# Breath.net
KiCad netlist of a schematic drawn in Altium Designer
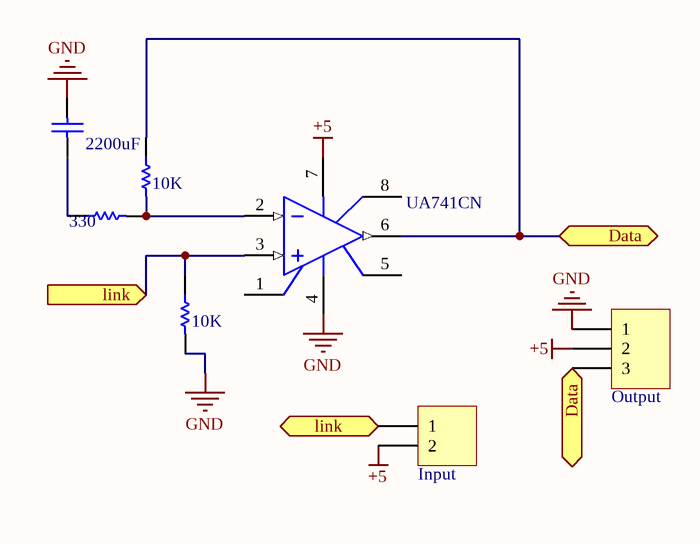
[diagram p0: Breath.SchDoc]

(export (version "E")
  (design (tool "Eeschema 10.0.6"))
  (components
    (comp (ref "10K Juga")
      (value "10K")
      (footprint "AXIAL-0.3")
      (description "Resistor")
      (fields (field (name "PUBLISHER") "Altium Limited"))
      (libsource (lib "Miscellaneous Devices") (part "Res1"))
    )
    (comp (ref "10K-2")
      (value "10K")
      (footprint "AXIAL-0.3")
      (description "Resistor")
      (fields (field (name "PUBLISHER") "Altium Limited"))
      (libsource (lib "Miscellaneous Devices") (part "Res1"))
    )
    (comp (ref "330-2")
      (value "330")
      (footprint "AXIAL-0.3")
      (description "Resistor")
      (fields (field (name "PUBLISHER") "Altium Limited"))
      (libsource (lib "Miscellaneous Devices") (part "Res1"))
    )
    (comp (ref "2200uF")
      (value "2200uF")
      (footprint "RAD-0.3")
      (description "Capacitor")
      (fields (field (name "PUBLISHER") "Altium Limited"))
      (libsource (lib "Miscellaneous Devices") (part "Cap"))
    )
    (comp (ref "o")
      (value "Output")
      (footprint "My_1X03")
      (description "Header, 3-Pin")
      (fields (field (name "PUBLISHER") "Altium Limited"))
      (libsource (lib "Mylib") (part "Header 3"))
    )
    (comp (ref "PPP")
      (value "Input")
      (footprint "HDR1X2")
      (description "Header, 2-Pin")
      (fields (field (name "PUBLISHER") "Altium Limited"))
      (libsource (lib "Mylib") (part "Header 2"))
    )
    (comp (ref "UA741CN")
      (value "UA741CN")
      (footprint "DIP8")
      (description "General-Purpose Single Operational Amplifier")
      (fields (field (name "PUBLISHER") "Altium Limited"))
      (libsource (lib "ST Operational Amplifier") (part "UA741CN"))
    )
  )
  (nets
    (net (code "1") (name "+5") (class "Default")
      (node (ref "PPP") (pin "2") (pinfunction "2_2") (pintype "passive"))
      (node (ref "UA741CN") (pin "7") (pinfunction "V+_7") (pintype "power_in"))
      (node (ref "o") (pin "2") (pinfunction "2_2") (pintype "passive"))
    )
    (net (code "2") (name "/Data") (class "Default")
      (node (ref "10K Juga") (pin "1") (pinfunction "1_1") (pintype "passive"))
      (node (ref "UA741CN") (pin "6") (pinfunction "OUT_6") (pintype "output"))
      (node (ref "o") (pin "3") (pinfunction "3_3") (pintype "passive"))
    )
    (net (code "3") (name "/link") (class "Default")
      (node (ref "10K-2") (pin "1") (pinfunction "1_1") (pintype "passive"))
      (node (ref "PPP") (pin "1") (pinfunction "1_1") (pintype "passive"))
      (node (ref "UA741CN") (pin "3") (pinfunction "IN+_3") (pintype "input"))
    )
    (net (code "4") (name "GND") (class "Default")
      (node (ref "10K-2") (pin "2") (pinfunction "2_2") (pintype "passive"))
      (node (ref "2200uF") (pin "2") (pinfunction "2_2") (pintype "passive"))
      (node (ref "UA741CN") (pin "4") (pinfunction "V-_4") (pintype "power_in"))
      (node (ref "o") (pin "1") (pinfunction "1_1") (pintype "passive"))
    )
    (net (code "5") (name "Net-(2200uF-Pad1)") (class "Default")
      (node (ref "2200uF") (pin "1") (pinfunction "1_1") (pintype "passive"))
      (node (ref "330-2") (pin "1") (pinfunction "1_1") (pintype "passive"))
    )
    (net (code "6") (name "Net-(UA741CN-IN-)") (class "Default")
      (node (ref "10K Juga") (pin "2") (pinfunction "2_2") (pintype "passive"))
      (node (ref "330-2") (pin "2") (pinfunction "2_2") (pintype "passive"))
      (node (ref "UA741CN") (pin "2") (pinfunction "IN-_2") (pintype "input"))
    )
    (net (code "7") (name "unconnected-(UA741CN-NC-Pad8)") (class "Default")
      (node (ref "UA741CN") (pin "8") (pinfunction "NC_8") (pintype "passive"))
    )
    (net (code "8") (name "unconnected-(UA741CN-OS_NULL-Pad1)") (class "Default")
      (node (ref "UA741CN") (pin "1") (pinfunction "OS_NULL_1") (pintype "passive"))
    )
    (net (code "9") (name "unconnected-(UA741CN-OS_NULL-Pad5)") (class "Default")
      (node (ref "UA741CN") (pin "5") (pinfunction "OS_NULL_5") (pintype "passive"))
    )
  )
)
